# STLINK_V3EC.net
KiCad netlist of a schematic drawn in Altium Designer
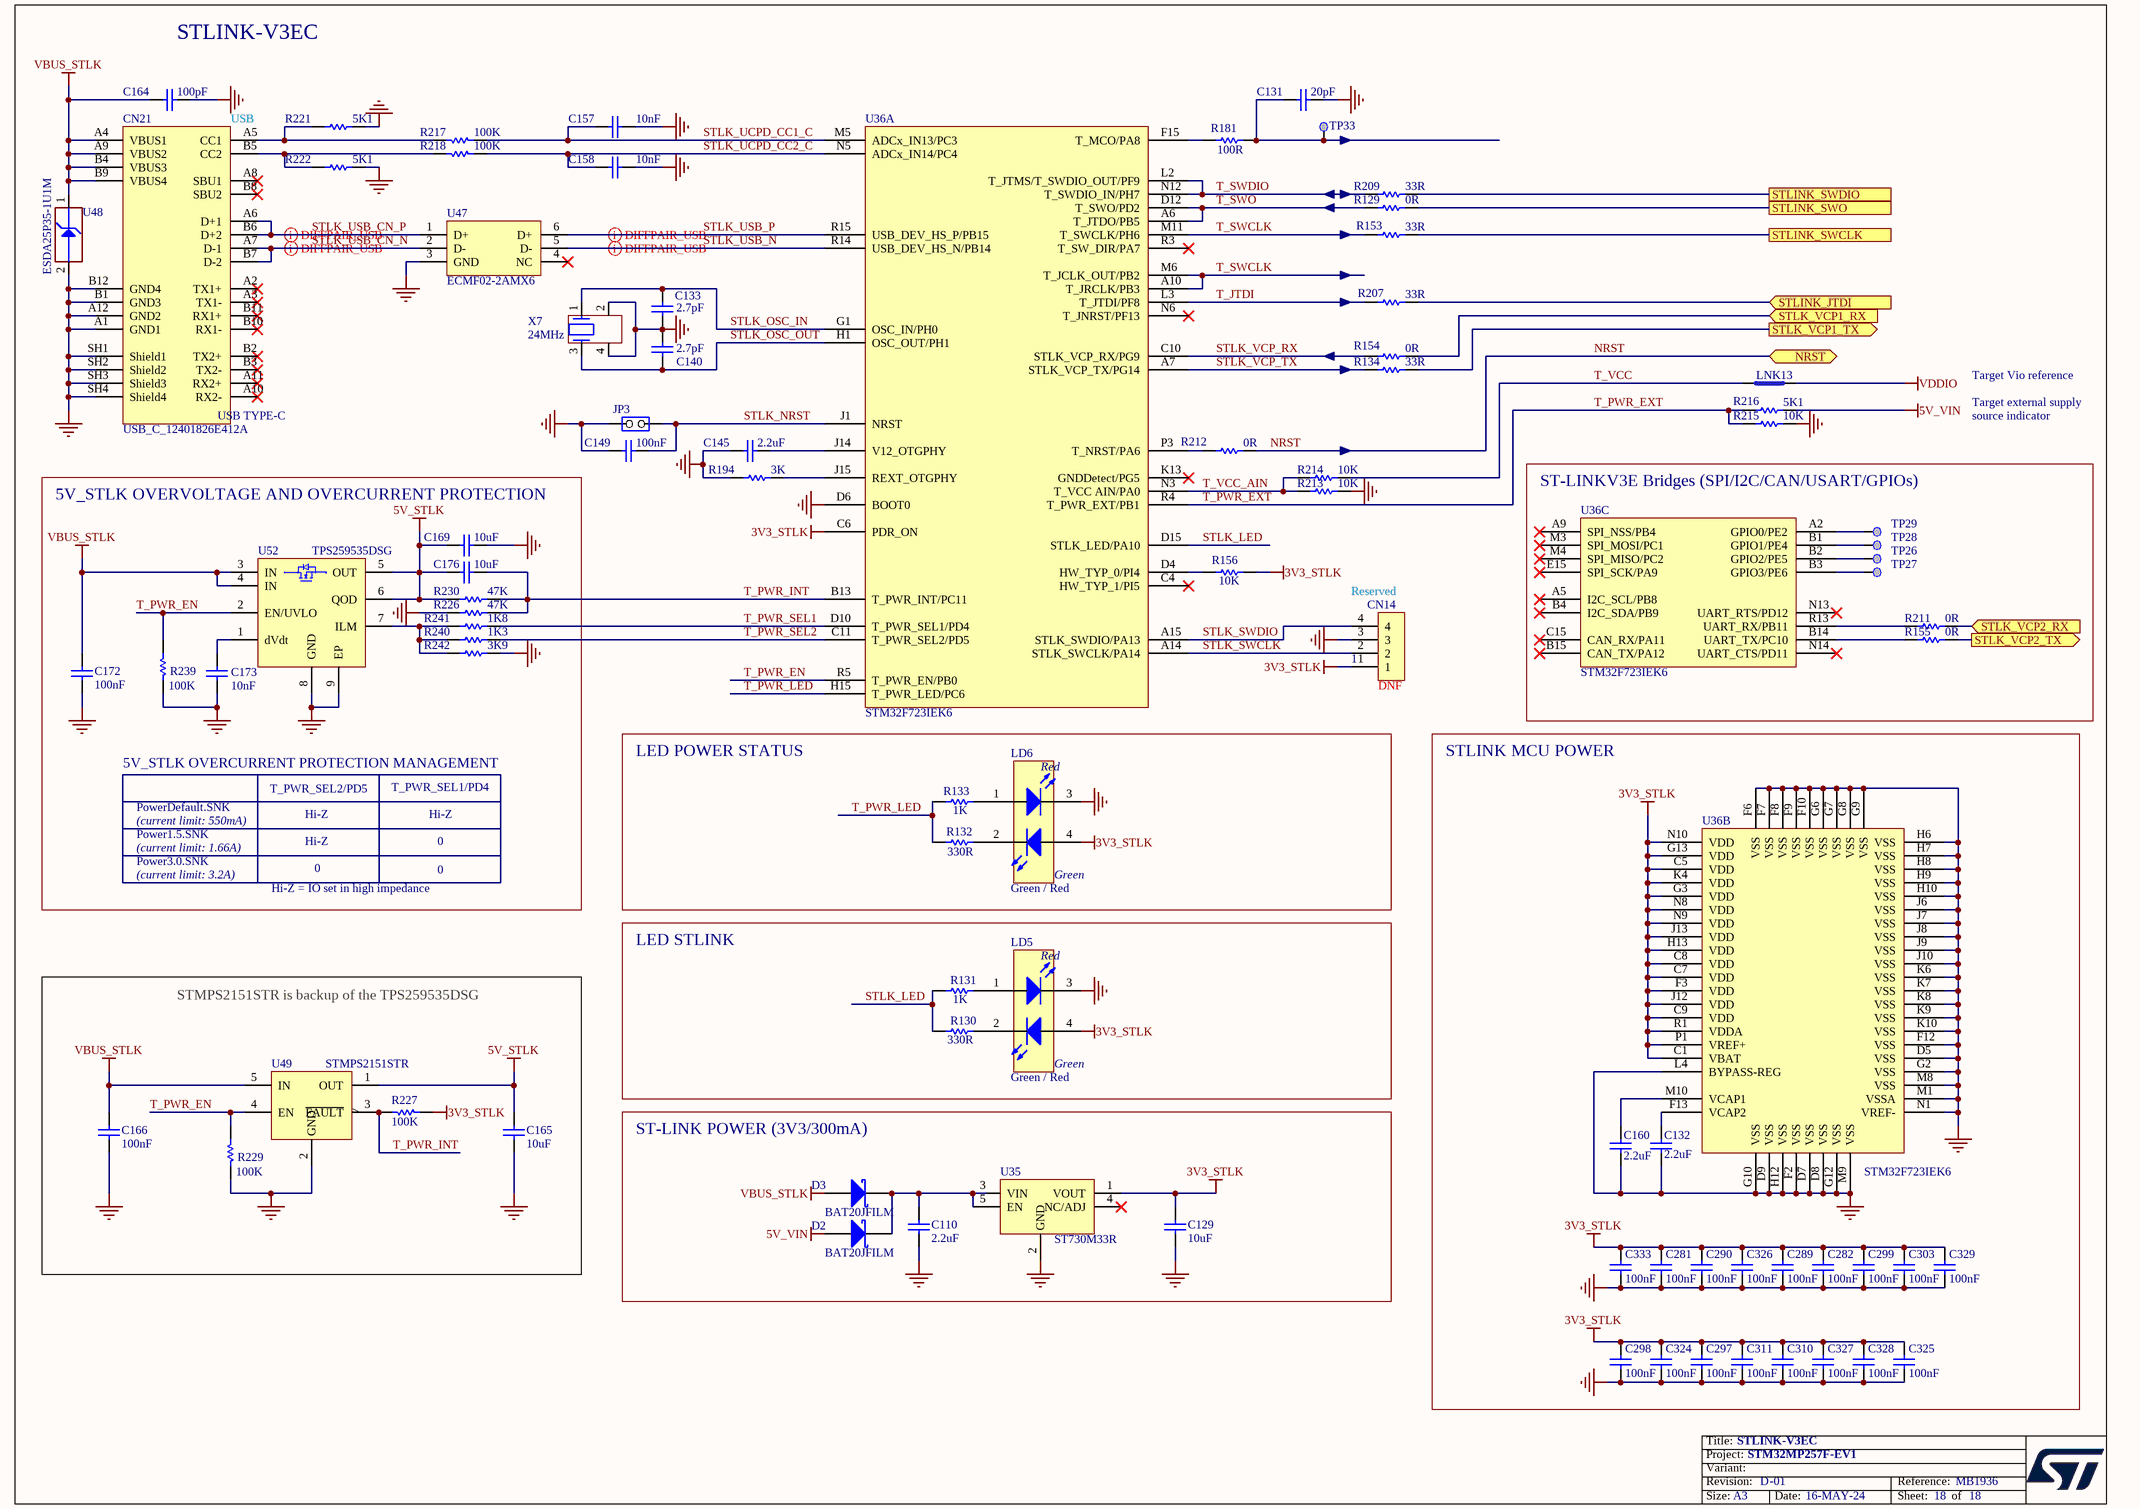
[diagram p0: STLINK_V3EC.SchDoc]

(export (version "E")
  (design (tool "Eeschema 10.0.6"))
  (components
    (comp (ref "C110")
      (value "2.2uF")
      (footprint "MCD_PARTS:C0805")
      (description "Capacitor, MLCC, 2.2uF, 25V, X7R, +/-10%, 0805, T=1,25mm")
      (fields
        (field (name "INTERNAL_PART_NUMBER") "MCD-02372")
        (field (name "MANUFACTURER_PART_NUMBER") "GRM21BR71E225KE11L")
      )
      (libsource (lib "MCD_PARTS_database") (part "Capacitor"))
    )
    (comp (ref "C129")
      (value "10uF")
      (footprint "MCD_PARTS:C0603")
      (description "Capacitor, MLCC, 10uF, 10V, X5R, +/-10%, 0603, T=0.8mm")
      (fields (field (name "INTERNAL_PART_NUMBER") "MCD-00099") (field (name "MANUFACTURER") "MURATA"))
      (libsource (lib "MCD_PARTS_database") (part "Capacitor"))
    )
    (comp (ref "C131")
      (value "20pF")
      (footprint "MCD_PARTS:C0402")
      (description "Capacitor, MLCC, 20pF, 50V, NPO, +/- 5%, 0402, T=0.5mm")
      (fields
        (field (name "INTERNAL_PART_NUMBER") "MCD-00016")
        (field (name "MANUFACTURER_PART_NUMBER") "CC0402JRNPO9BN200")
      )
      (libsource (lib "MCD_PARTS_database") (part "Capacitor"))
    )
    (comp (ref "C132")
      (value "2.2uF")
      (footprint "MCD_PARTS:C0402")
      (description "Capacitor, MLCC, 2.2uF, 6.3V, X5R, +/-10%, 0402, T=0.5mm")
      (fields (field (name "INTERNAL_PART_NUMBER") "MCD-02606") (field (name "MANUFACTURER") "YAGEO"))
      (libsource (lib "MCD_PARTS_database") (part "Capacitor"))
    )
    (comp (ref "C133")
      (value "2.7pF")
      (footprint "MCD_PARTS:C0402")
      (description "Capacitor, MLCC, 2.7pF, 50V, NPO, +/-0.1pF, 0402, T=0.5mm")
      (fields (field (name "INTERNAL_PART_NUMBER") "MCD-01774") (field (name "MANUFACTURER") "YAGEO"))
      (libsource (lib "MCD_PARTS_database") (part "Capacitor"))
    )
    (comp (ref "C140")
      (value "2.7pF")
      (footprint "MCD_PARTS:C0402")
      (description "Capacitor, MLCC, 2.7pF, 50V, NPO, +/-0.1pF, 0402, T=0.5mm")
      (fields (field (name "INTERNAL_PART_NUMBER") "MCD-01774") (field (name "MANUFACTURER") "YAGEO"))
      (libsource (lib "MCD_PARTS_database") (part "Capacitor"))
    )
    (comp (ref "C145")
      (value "2.2uF")
      (footprint "MCD_PARTS:C0402")
      (description "Capacitor, MLCC, 2.2uF, 6.3V, X5R, +/-10%, 0402, T=0.5mm")
      (fields (field (name "INTERNAL_PART_NUMBER") "MCD-02606") (field (name "MANUFACTURER") "YAGEO"))
      (libsource (lib "MCD_PARTS_database") (part "Capacitor"))
    )
    (comp (ref "C149")
      (value "100nF")
      (footprint "MCD_PARTS:C0402")
      (description "Capacitor, MLCC, 100nF, 16V, X7R, +/-10%, 0402, T=0.5mm")
      (fields
        (field (name "INTERNAL_PART_NUMBER") "MCD-00006")
        (field (name "MANUFACTURER_PART_NUMBER") "CC0402KRX7R7BB104")
      )
      (libsource (lib "MCD_PARTS_database") (part "Capacitor"))
    )
    (comp (ref "C157")
      (value "10nF")
      (footprint "MCD_PARTS:C0402")
      (description "Capacitor, MLCC, 10nF, 50V, X7R, +/-10%, 0402, T=0.5mm")
      (fields (field (name "INTERNAL_PART_NUMBER") "MCD-02198") (field (name "MANUFACTURER") "YAGEO"))
      (libsource (lib "MCD_PARTS_database") (part "Capacitor"))
    )
    (comp (ref "C158")
      (value "10nF")
      (footprint "MCD_PARTS:C0402")
      (description "Capacitor, MLCC, 10nF, 50V, X7R, +/-10%, 0402, T=0.5mm")
      (fields (field (name "INTERNAL_PART_NUMBER") "MCD-02198") (field (name "MANUFACTURER") "YAGEO"))
      (libsource (lib "MCD_PARTS_database") (part "Capacitor"))
    )
    (comp (ref "C160")
      (value "2.2uF")
      (footprint "MCD_PARTS:C0402")
      (description "Capacitor, MLCC, 2.2uF, 6.3V, X5R, +/-10%, 0402, T=0.5mm")
      (fields (field (name "INTERNAL_PART_NUMBER") "MCD-02606") (field (name "MANUFACTURER") "YAGEO"))
      (libsource (lib "MCD_PARTS_database") (part "Capacitor"))
    )
    (comp (ref "C164")
      (value "100pF")
      (footprint "MCD_PARTS:C0402")
      (description "Capacitor, MLCC, 100pF, 50V, NPO, +/-5%, 0402, T=0.5mm")
      (fields (field (name "INTERNAL_PART_NUMBER") "MCD-00205") (field (name "MANUFACTURER") "YAGEO"))
      (libsource (lib "MCD_PARTS_database") (part "Capacitor"))
    )
    (comp (ref "C165")
      (value "10uF")
      (footprint "MCD_PARTS:C0603")
      (description "Capacitor, MLCC, 10uF, 10V, X5R, +/-10%, 0603, T=0.8mm")
      (fields (field (name "INTERNAL_PART_NUMBER") "MCD-00099") (field (name "MANUFACTURER") "MURATA"))
      (libsource (lib "MCD_PARTS_database") (part "Capacitor"))
    )
    (comp (ref "C166")
      (value "100nF")
      (footprint "MCD_PARTS:C0402")
      (description "Capacitor, MLCC, 100nF, 25V, X7R, +/-10%, 0402, T=0.5mm")
      (fields (field (name "INTERNAL_PART_NUMBER") "MCD-02355") (field (name "MANUFACTURER") "WALSIN"))
      (libsource (lib "MCD_PARTS_database") (part "Capacitor"))
    )
    (comp (ref "C169")
      (value "10uF")
      (footprint "MCD_PARTS:C0603")
      (description "Capacitor, MLCC, 10uF, 10V, X5R, +/-10%, 0603, T=0.8mm")
      (fields (field (name "INTERNAL_PART_NUMBER") "MCD-00099") (field (name "MANUFACTURER") "MURATA"))
      (libsource (lib "MCD_PARTS_database") (part "Capacitor"))
    )
    (comp (ref "C172")
      (value "100nF")
      (footprint "MCD_PARTS:C0402")
      (description "Capacitor, MLCC, 100nF, 25V, X7R, +/-10%, 0402, T=0.5mm")
      (fields (field (name "INTERNAL_PART_NUMBER") "MCD-02355") (field (name "MANUFACTURER") "WALSIN"))
      (libsource (lib "MCD_PARTS_database") (part "Capacitor"))
    )
    (comp (ref "C173")
      (value "10nF")
      (footprint "MCD_PARTS:C0402")
      (description "Capacitor, MLCC, 10nF, 50V, X7R, +/-10%, 0402, T=0.5mm")
      (fields (field (name "INTERNAL_PART_NUMBER") "MCD-02198") (field (name "MANUFACTURER") "YAGEO"))
      (libsource (lib "MCD_PARTS_database") (part "Capacitor"))
    )
    (comp (ref "C176")
      (value "10uF")
      (footprint "MCD_PARTS:C0402")
      (description "Capacitor, MLCC, 10uF, 6.3V, X5R, +/-20%, 0402, T=0.5mm")
      (fields (field (name "INTERNAL_PART_NUMBER") "MCD-03140") (field (name "MANUFACTURER") "MURATA"))
      (libsource (lib "MCD_PARTS_database") (part "Capacitor"))
    )
    (comp (ref "C281")
      (value "100nF")
      (footprint "MCD_PARTS:C0402")
      (description "Capacitor, MLCC, 100nF, 16V, X7R, +/-10%, 0402, T=0.5mm")
      (fields
        (field (name "INTERNAL_PART_NUMBER") "MCD-00006")
        (field (name "MANUFACTURER_PART_NUMBER") "CC0402KRX7R7BB104")
      )
      (libsource (lib "MCD_PARTS_database") (part "Capacitor"))
    )
    (comp (ref "C282")
      (value "100nF")
      (footprint "MCD_PARTS:C0402")
      (description "Capacitor, MLCC, 100nF, 16V, X7R, +/-10%, 0402, T=0.5mm")
      (fields
        (field (name "INTERNAL_PART_NUMBER") "MCD-00006")
        (field (name "MANUFACTURER_PART_NUMBER") "CC0402KRX7R7BB104")
      )
      (libsource (lib "MCD_PARTS_database") (part "Capacitor"))
    )
    (comp (ref "C289")
      (value "100nF")
      (footprint "MCD_PARTS:C0402")
      (description "Capacitor, MLCC, 100nF, 16V, X7R, +/-10%, 0402, T=0.5mm")
      (fields
        (field (name "INTERNAL_PART_NUMBER") "MCD-00006")
        (field (name "MANUFACTURER_PART_NUMBER") "CC0402KRX7R7BB104")
      )
      (libsource (lib "MCD_PARTS_database") (part "Capacitor"))
    )
    (comp (ref "C290")
      (value "100nF")
      (footprint "MCD_PARTS:C0402")
      (description "Capacitor, MLCC, 100nF, 16V, X7R, +/-10%, 0402, T=0.5mm")
      (fields
        (field (name "INTERNAL_PART_NUMBER") "MCD-00006")
        (field (name "MANUFACTURER_PART_NUMBER") "CC0402KRX7R7BB104")
      )
      (libsource (lib "MCD_PARTS_database") (part "Capacitor"))
    )
    (comp (ref "C297")
      (value "100nF")
      (footprint "MCD_PARTS:C0402")
      (description "Capacitor, MLCC, 100nF, 16V, X7R, +/-10%, 0402, T=0.5mm")
      (fields
        (field (name "INTERNAL_PART_NUMBER") "MCD-00006")
        (field (name "MANUFACTURER_PART_NUMBER") "CC0402KRX7R7BB104")
      )
      (libsource (lib "MCD_PARTS_database") (part "Capacitor"))
    )
    (comp (ref "C298")
      (value "100nF")
      (footprint "MCD_PARTS:C0402")
      (description "Capacitor, MLCC, 100nF, 16V, X7R, +/-10%, 0402, T=0.5mm")
      (fields
        (field (name "INTERNAL_PART_NUMBER") "MCD-00006")
        (field (name "MANUFACTURER_PART_NUMBER") "CC0402KRX7R7BB104")
      )
      (libsource (lib "MCD_PARTS_database") (part "Capacitor"))
    )
    (comp (ref "C299")
      (value "100nF")
      (footprint "MCD_PARTS:C0402")
      (description "Capacitor, MLCC, 100nF, 16V, X7R, +/-10%, 0402, T=0.5mm")
      (fields
        (field (name "INTERNAL_PART_NUMBER") "MCD-00006")
        (field (name "MANUFACTURER_PART_NUMBER") "CC0402KRX7R7BB104")
      )
      (libsource (lib "MCD_PARTS_database") (part "Capacitor"))
    )
    (comp (ref "C303")
      (value "100nF")
      (footprint "MCD_PARTS:C0402")
      (description "Capacitor, MLCC, 100nF, 16V, X7R, +/-10%, 0402, T=0.5mm")
      (fields
        (field (name "INTERNAL_PART_NUMBER") "MCD-00006")
        (field (name "MANUFACTURER_PART_NUMBER") "CC0402KRX7R7BB104")
      )
      (libsource (lib "MCD_PARTS_database") (part "Capacitor"))
    )
    (comp (ref "C310")
      (value "100nF")
      (footprint "MCD_PARTS:C0402")
      (description "Capacitor, MLCC, 100nF, 16V, X7R, +/-10%, 0402, T=0.5mm")
      (fields
        (field (name "INTERNAL_PART_NUMBER") "MCD-00006")
        (field (name "MANUFACTURER_PART_NUMBER") "CC0402KRX7R7BB104")
      )
      (libsource (lib "MCD_PARTS_database") (part "Capacitor"))
    )
    (comp (ref "C311")
      (value "100nF")
      (footprint "MCD_PARTS:C0402")
      (description "Capacitor, MLCC, 100nF, 16V, X7R, +/-10%, 0402, T=0.5mm")
      (fields
        (field (name "INTERNAL_PART_NUMBER") "MCD-00006")
        (field (name "MANUFACTURER_PART_NUMBER") "CC0402KRX7R7BB104")
      )
      (libsource (lib "MCD_PARTS_database") (part "Capacitor"))
    )
    (comp (ref "C324")
      (value "100nF")
      (footprint "MCD_PARTS:C0402")
      (description "Capacitor, MLCC, 100nF, 16V, X7R, +/-10%, 0402, T=0.5mm")
      (fields
        (field (name "INTERNAL_PART_NUMBER") "MCD-00006")
        (field (name "MANUFACTURER_PART_NUMBER") "CC0402KRX7R7BB104")
      )
      (libsource (lib "MCD_PARTS_database") (part "Capacitor"))
    )
    (comp (ref "C325")
      (value "100nF")
      (footprint "MCD_PARTS:C0402")
      (description "Capacitor, MLCC, 100nF, 16V, X7R, +/-10%, 0402, T=0.5mm")
      (fields
        (field (name "INTERNAL_PART_NUMBER") "MCD-00006")
        (field (name "MANUFACTURER_PART_NUMBER") "CC0402KRX7R7BB104")
      )
      (libsource (lib "MCD_PARTS_database") (part "Capacitor"))
    )
    (comp (ref "C326")
      (value "100nF")
      (footprint "MCD_PARTS:C0402")
      (description "Capacitor, MLCC, 100nF, 16V, X7R, +/-10%, 0402, T=0.5mm")
      (fields
        (field (name "INTERNAL_PART_NUMBER") "MCD-00006")
        (field (name "MANUFACTURER_PART_NUMBER") "CC0402KRX7R7BB104")
      )
      (libsource (lib "MCD_PARTS_database") (part "Capacitor"))
    )
    (comp (ref "C327")
      (value "100nF")
      (footprint "MCD_PARTS:C0402")
      (description "Capacitor, MLCC, 100nF, 16V, X7R, +/-10%, 0402, T=0.5mm")
      (fields
        (field (name "INTERNAL_PART_NUMBER") "MCD-00006")
        (field (name "MANUFACTURER_PART_NUMBER") "CC0402KRX7R7BB104")
      )
      (libsource (lib "MCD_PARTS_database") (part "Capacitor"))
    )
    (comp (ref "C328")
      (value "100nF")
      (footprint "MCD_PARTS:C0402")
      (description "Capacitor, MLCC, 100nF, 16V, X7R, +/-10%, 0402, T=0.5mm")
      (fields
        (field (name "INTERNAL_PART_NUMBER") "MCD-00006")
        (field (name "MANUFACTURER_PART_NUMBER") "CC0402KRX7R7BB104")
      )
      (libsource (lib "MCD_PARTS_database") (part "Capacitor"))
    )
    (comp (ref "C329")
      (value "100nF")
      (footprint "MCD_PARTS:C0402")
      (description "Capacitor, MLCC, 100nF, 16V, X7R, +/-10%, 0402, T=0.5mm")
      (fields
        (field (name "INTERNAL_PART_NUMBER") "MCD-00006")
        (field (name "MANUFACTURER_PART_NUMBER") "CC0402KRX7R7BB104")
      )
      (libsource (lib "MCD_PARTS_database") (part "Capacitor"))
    )
    (comp (ref "C333")
      (value "100nF")
      (footprint "MCD_PARTS:C0402")
      (description "Capacitor, MLCC, 100nF, 16V, X7R, +/-10%, 0402, T=0.5mm")
      (fields
        (field (name "INTERNAL_PART_NUMBER") "MCD-00006")
        (field (name "MANUFACTURER_PART_NUMBER") "CC0402KRX7R7BB104")
      )
      (libsource (lib "MCD_PARTS_database") (part "Capacitor"))
    )
    (comp (ref "CN14")
      (value "Header 4x1")
      (footprint "MCD_PARTS:CON_SAMTEC_TSW-104-07-G-S")
      (description "Header, 4x1, 2.54mm, VR, TH, T=5.84mm/2.54mm")
      (fields
        (field (name "INTERNAL_PART_NUMBER") "MCD-00029")
        (field (name "MANUFACTURER_PART_NUMBER") "TSW-104-07-G-S")
      )
      (libsource (lib "MCD_PARTS_database") (part "Header 4x1"))
    )
    (comp (ref "CN21")
      (value "USB_C_12401826E412A")
      (footprint "MCD_PARTS:CON_USB-TYPEC_AMPHENOL_12401826E412A")
      (description "USB_TypeC, 24 pins, RA, SMD, T=2.96mm")
      (fields (field (name "INTERNAL_PART_NUMBER") "MCD-03232") (field (name "MANUFACTURER") "AMPHENOL ICC"))
      (libsource (lib "MCD_PARTS_database") (part "USB_TYPE_C_Receptacle"))
    )
    (comp (ref "D2")
      (value "BAT20JFILM")
      (footprint "MCD_PARTS:DIO_SOD323_1A_2K")
      (description "Signal Schottky Diode, If=1A, Ifsm=5A, Vf =0.54V@1A, Vrrm=23V, Ir = 0.65µA@5V, SOD-323")
      (fields
        (field (name "INTERNAL_PART_NUMBER") "MCD-03011")
        (field (name "MANUFACTURER") "STMICROELECTRONICS")
      )
      (libsource (lib "MCD_PARTS_database") (part "SCHOTTKY_1A_2K"))
    )
    (comp (ref "D3")
      (value "BAT20JFILM")
      (footprint "MCD_PARTS:DIO_SOD323_1A_2K")
      (description "Signal Schottky Diode, If=1A, Ifsm=5A, Vf =0.54V@1A, Vrrm=23V, Ir = 0.65µA@5V, SOD-323")
      (fields
        (field (name "INTERNAL_PART_NUMBER") "MCD-03011")
        (field (name "MANUFACTURER") "STMICROELECTRONICS")
      )
      (libsource (lib "MCD_PARTS_database") (part "SCHOTTKY_1A_2K"))
    )
    (comp (ref "JP3")
      (value "Jumper_Header 2x1")
      (footprint "MCD_PARTS:CON_SAMTEC_TSW-102-07-G-S")
      (description "Header, 2x1, 2.54mm, VR, TH, T=5.84mm/2.54mm")
      (fields (field (name "INTERNAL_PART_NUMBER") "MCD-00045") (field (name "MANUFACTURER") "SAMTEC"))
      (libsource (lib "MCD_PARTS_database") (part "Jumper_Header 2x1"))
    )
    (comp (ref "LD5")
      (value "Green / Red")
      (footprint "MCD_PARTS:LED_BI-GR_WE-150141SV73110")
      (description "LED Bicolor, Green/Red, 2V, 20mA,  4-PLCC")
      (fields
        (field (name "INTERNAL_PART_NUMBER") "MCD-02631")
        (field (name "MANUFACTURER") "WURTH ELEKTRONIK")
      )
      (libsource (lib "MCD_PARTS_database") (part "LED_BICOLOR"))
    )
    (comp (ref "LD6")
      (value "Green / Red")
      (footprint "MCD_PARTS:LED_BI-GR_WE-150141SV73110")
      (description "LED Bicolor, Green/Red, 2V, 20mA,  4-PLCC")
      (fields
        (field (name "INTERNAL_PART_NUMBER") "MCD-02631")
        (field (name "MANUFACTURER") "WURTH ELEKTRONIK")
      )
      (libsource (lib "MCD_PARTS_database") (part "LED_BICOLOR"))
    )
    (comp (ref "LNK13")
      (value "link_200")
      (footprint "MCD_PARTS:LINK200")
      (description "Track link on PCB 200um width for layout routing. No component assembly and no component in BOM")
      (fields (field (name "INTERNAL_PART_NUMBER") "MCD-02777"))
      (libsource (lib "MCD_PARTS_database") (part "link_200"))
    )
    (comp (ref "R129")
      (value "0R")
      (footprint "MCD_PARTS:R0402")
      (description "Resistor, 0R, 0402, +/-5%, 1/16W")
      (fields (field (name "INTERNAL_PART_NUMBER") "MCD-00052") (field (name "MANUFACTURER") "YAGEO"))
      (libsource (lib "MCD_PARTS_database") (part "Resistor"))
    )
    (comp (ref "R130")
      (value "330R")
      (footprint "MCD_PARTS:R0402")
      (description "Resistor, 330R, 0402, +/-1%, 1/16W")
      (fields (field (name "INTERNAL_PART_NUMBER") "MCD-00062") (field (name "MANUFACTURER") "YAGEO"))
      (libsource (lib "MCD_PARTS_database") (part "Resistor"))
    )
    (comp (ref "R131")
      (value "1K")
      (footprint "MCD_PARTS:R0402")
      (description "Resistor, 1K, 0402, +/-0.1%, 1/16W, +/-25ppm/°C")
      (fields (field (name "INTERNAL_PART_NUMBER") "MCD-02665") (field (name "MANUFACTURER") "YAGEO"))
      (libsource (lib "MCD_PARTS_database") (part "Resistor"))
    )
    (comp (ref "R132")
      (value "330R")
      (footprint "MCD_PARTS:R0402")
      (description "Resistor, 330R, 0402, +/-1%, 1/16W")
      (fields (field (name "INTERNAL_PART_NUMBER") "MCD-00062") (field (name "MANUFACTURER") "YAGEO"))
      (libsource (lib "MCD_PARTS_database") (part "Resistor"))
    )
    (comp (ref "R133")
      (value "1K")
      (footprint "MCD_PARTS:R0402")
      (description "Resistor, 1K, 0402, +/-0.1%, 1/16W, +/-25ppm/°C")
      (fields (field (name "INTERNAL_PART_NUMBER") "MCD-02665") (field (name "MANUFACTURER") "YAGEO"))
      (libsource (lib "MCD_PARTS_database") (part "Resistor"))
    )
    (comp (ref "R134")
      (value "33R")
      (footprint "MCD_PARTS:R0402")
      (description "Resistor, 33R, 0402, +/-1%, 1/16W")
      (fields (field (name "INTERNAL_PART_NUMBER") "MCD-00455") (field (name "MANUFACTURER") "YAGEO"))
      (libsource (lib "MCD_PARTS_database") (part "Resistor"))
    )
    (comp (ref "R153")
      (value "33R")
      (footprint "MCD_PARTS:R0402")
      (description "Resistor, 33R, 0402, +/-1%, 1/16W")
      (fields (field (name "INTERNAL_PART_NUMBER") "MCD-00455") (field (name "MANUFACTURER") "YAGEO"))
      (libsource (lib "MCD_PARTS_database") (part "Resistor"))
    )
    (comp (ref "R154")
      (value "0R")
      (footprint "MCD_PARTS:R0402")
      (description "Resistor, 0R, 0402, +/-5%, 1/16W")
      (fields (field (name "INTERNAL_PART_NUMBER") "MCD-00052") (field (name "MANUFACTURER") "YAGEO"))
      (libsource (lib "MCD_PARTS_database") (part "Resistor"))
    )
    (comp (ref "R155")
      (value "0R")
      (footprint "MCD_PARTS:R0402")
      (description "Resistor, 0R, 0402, +/-5%, 1/16W")
      (fields
        (field (name "INTERNAL_PART_NUMBER") "MCD-00052")
        (field (name "MANUFACTURER_PART_NUMBER") "RC0402JR-070RL")
      )
      (libsource (lib "MCD_PARTS_database") (part "Resistor"))
    )
    (comp (ref "R156")
      (value "10K")
      (footprint "MCD_PARTS:R0402")
      (description "Resistor, 10K, 0402, +/-1%, 1/16W")
      (fields
        (field (name "INTERNAL_PART_NUMBER") "MCD-00053")
        (field (name "MANUFACTURER_PART_NUMBER") "RC0402FR-0710KL")
      )
      (libsource (lib "MCD_PARTS_database") (part "Resistor"))
    )
    (comp (ref "R181")
      (value "100R")
      (footprint "MCD_PARTS:R0402")
      (description "Resistor, 100R, 0402, +/- 1%, 1/16W")
      (fields (field (name "INTERNAL_PART_NUMBER") "MCD-00067") (field (name "MANUFACTURER") "YAGEO"))
      (libsource (lib "MCD_PARTS_database") (part "Resistor"))
    )
    (comp (ref "R194")
      (value "3K")
      (footprint "MCD_PARTS:R0402")
      (description "Resistor, 3K, 0402, +/-1%, 1/16W")
      (fields
        (field (name "INTERNAL_PART_NUMBER") "MCD-00185")
        (field (name "MANUFACTURER_PART_NUMBER") "RC0402FR-073KL")
      )
      (libsource (lib "MCD_PARTS_database") (part "Resistor"))
    )
    (comp (ref "R207")
      (value "33R")
      (footprint "MCD_PARTS:R0402")
      (description "Resistor, 33R, 0402, +/-1%, 1/16W")
      (fields (field (name "INTERNAL_PART_NUMBER") "MCD-00455") (field (name "MANUFACTURER") "YAGEO"))
      (libsource (lib "MCD_PARTS_database") (part "Resistor"))
    )
    (comp (ref "R209")
      (value "33R")
      (footprint "MCD_PARTS:R0402")
      (description "Resistor, 33R, 0402, +/-1%, 1/16W")
      (fields (field (name "INTERNAL_PART_NUMBER") "MCD-00455") (field (name "MANUFACTURER") "YAGEO"))
      (libsource (lib "MCD_PARTS_database") (part "Resistor"))
    )
    (comp (ref "R211")
      (value "0R")
      (footprint "MCD_PARTS:R0402")
      (description "Resistor, 0R, 0402, +/-5%, 1/16W")
      (fields
        (field (name "INTERNAL_PART_NUMBER") "MCD-00052")
        (field (name "MANUFACTURER_PART_NUMBER") "RC0402JR-070RL")
      )
      (libsource (lib "MCD_PARTS_database") (part "Resistor"))
    )
    (comp (ref "R212")
      (value "0R")
      (footprint "MCD_PARTS:R0402")
      (description "Resistor, 0R, 0402, +/-5%, 1/16W")
      (fields (field (name "INTERNAL_PART_NUMBER") "MCD-00052") (field (name "MANUFACTURER") "YAGEO"))
      (libsource (lib "MCD_PARTS_database") (part "Resistor"))
    )
    (comp (ref "R213")
      (value "10K")
      (footprint "MCD_PARTS:R0402")
      (description "Resistor, 10K, 0402, +/-1%, 1/16W")
      (fields
        (field (name "INTERNAL_PART_NUMBER") "MCD-00053")
        (field (name "MANUFACTURER_PART_NUMBER") "RC0402FR-0710KL")
      )
      (libsource (lib "MCD_PARTS_database") (part "Resistor"))
    )
    (comp (ref "R214")
      (value "10K")
      (footprint "MCD_PARTS:R0402")
      (description "Resistor, 10K, 0402, +/-1%, 1/16W")
      (fields
        (field (name "INTERNAL_PART_NUMBER") "MCD-00053")
        (field (name "MANUFACTURER_PART_NUMBER") "RC0402FR-0710KL")
      )
      (libsource (lib "MCD_PARTS_database") (part "Resistor"))
    )
    (comp (ref "R215")
      (value "10K")
      (footprint "MCD_PARTS:R0402")
      (description "Resistor, 10K, 0402, +/-1%, 1/16W")
      (fields
        (field (name "INTERNAL_PART_NUMBER") "MCD-00053")
        (field (name "MANUFACTURER_PART_NUMBER") "RC0402FR-0710KL")
      )
      (libsource (lib "MCD_PARTS_database") (part "Resistor"))
    )
    (comp (ref "R216")
      (value "5K1")
      (footprint "MCD_PARTS:R0402")
      (description "Resistor, 5K1, 0402, +/-1%, 1/16W")
      (fields (field (name "INTERNAL_PART_NUMBER") "MCD-00333") (field (name "MANUFACTURER") "YAGEO"))
      (libsource (lib "MCD_PARTS_database") (part "Resistor"))
    )
    (comp (ref "R217")
      (value "100K")
      (footprint "MCD_PARTS:R0402")
      (description "Resistor, 100K, 0402, +/-1%, 1/16W")
      (fields
        (field (name "INTERNAL_PART_NUMBER") "MCD-00059")
        (field (name "MANUFACTURER_PART_NUMBER") "RC0402FR-07100KL")
      )
      (libsource (lib "MCD_PARTS_database") (part "Resistor"))
    )
    (comp (ref "R218")
      (value "100K")
      (footprint "MCD_PARTS:R0402")
      (description "Resistor, 100K, 0402, +/-1%, 1/16W")
      (fields
        (field (name "INTERNAL_PART_NUMBER") "MCD-00059")
        (field (name "MANUFACTURER_PART_NUMBER") "RC0402FR-07100KL")
      )
      (libsource (lib "MCD_PARTS_database") (part "Resistor"))
    )
    (comp (ref "R221")
      (value "5K1")
      (footprint "MCD_PARTS:R0402")
      (description "Resistor, 5K1, 0402, +/-1%, 1/16W")
      (fields (field (name "INTERNAL_PART_NUMBER") "MCD-00333") (field (name "MANUFACTURER") "YAGEO"))
      (libsource (lib "MCD_PARTS_database") (part "Resistor"))
    )
    (comp (ref "R222")
      (value "5K1")
      (footprint "MCD_PARTS:R0402")
      (description "Resistor, 5K1, 0402, +/-1%, 1/16W")
      (fields (field (name "INTERNAL_PART_NUMBER") "MCD-00333") (field (name "MANUFACTURER") "YAGEO"))
      (libsource (lib "MCD_PARTS_database") (part "Resistor"))
    )
    (comp (ref "R226")
      (value "47K")
      (footprint "MCD_PARTS:R0402")
      (description "Resistor,47K,0402,1%,1/16W")
      (fields
        (field (name "INTERNAL_PART_NUMBER") "MCD-00063")
        (field (name "MANUFACTURER_PART_NUMBER") "RC0402FR-0747KL")
        (field (name "PROVIDED_BY") "SUBCO")
      )
      (libsource (lib "MCD_PARTS_database") (part "Resistor"))
    )
    (comp (ref "R227")
      (value "100K")
      (footprint "MCD_PARTS:R0402")
      (description "Resistor, 100K, 0402, +/-1%, 1/16W")
      (fields
        (field (name "INTERNAL_PART_NUMBER") "MCD-00059")
        (field (name "MANUFACTURER_PART_NUMBER") "RC0402FR-07100KL")
      )
      (libsource (lib "MCD_PARTS_database") (part "Resistor"))
    )
    (comp (ref "R229")
      (value "100K")
      (footprint "MCD_PARTS:R0402")
      (description "Resistor, 100K, 0402, +/-1%, 1/16W")
      (fields
        (field (name "INTERNAL_PART_NUMBER") "MCD-00059")
        (field (name "MANUFACTURER_PART_NUMBER") "RC0402FR-07100KL")
      )
      (libsource (lib "MCD_PARTS_database") (part "Resistor"))
    )
    (comp (ref "R230")
      (value "47K")
      (footprint "MCD_PARTS:R0402")
      (description "Resistor,47K,0402,1%,1/16W")
      (fields
        (field (name "INTERNAL_PART_NUMBER") "MCD-00063")
        (field (name "MANUFACTURER_PART_NUMBER") "RC0402FR-0747KL")
        (field (name "PROVIDED_BY") "SUBCO")
      )
      (libsource (lib "MCD_PARTS_database") (part "Resistor"))
    )
    (comp (ref "R239")
      (value "100K")
      (footprint "MCD_PARTS:R0402")
      (description "Resistor, 100K, 0402, +/-1%, 1/16W")
      (fields
        (field (name "INTERNAL_PART_NUMBER") "MCD-00059")
        (field (name "MANUFACTURER_PART_NUMBER") "RC0402FR-07100KL")
      )
      (libsource (lib "MCD_PARTS_database") (part "Resistor"))
    )
    (comp (ref "R240")
      (value "1K3")
      (footprint "MCD_PARTS:R0402")
      (description "Resistor, 1K3, 0402, +/-1%, 1/16W")
      (fields (field (name "INTERNAL_PART_NUMBER") "MCD-00381") (field (name "MANUFACTURER") "YAGEO"))
      (libsource (lib "MCD_PARTS_database") (part "Resistor"))
    )
    (comp (ref "R241")
      (value "1K8")
      (footprint "MCD_PARTS:R0402")
      (description "Resistor, 1K8, 0402, +/-1%, 1/16W")
      (fields (field (name "INTERNAL_PART_NUMBER") "MCD-00409") (field (name "MANUFACTURER") "YAGEO"))
      (libsource (lib "MCD_PARTS_database") (part "Resistor"))
    )
    (comp (ref "R242")
      (value "3K9")
      (footprint "MCD_PARTS:R0402")
      (description "Resistor, 3K9, 0402, +/-1%, 1/16W, +/-100ppm/°C")
      (fields (field (name "INTERNAL_PART_NUMBER") "MCD-02455") (field (name "MANUFACTURER") "YAGEO"))
      (libsource (lib "MCD_PARTS_database") (part "Resistor"))
    )
    (comp (ref "TP26")
      (value "Test Point")
      (footprint "MCD_PARTS:TP_SMD_1MM")
      (description "Test Point 1mm")
      (fields
        (field (name "INTERNAL_PART_NUMBER") "MCD-00074")
        (field (name "MANUFACTURER_PART_NUMBER") "n/a")
      )
      (libsource (lib "MCD_PARTS_database") (part "Test Point"))
    )
    (comp (ref "TP27")
      (value "Test Point")
      (footprint "MCD_PARTS:TP_SMD_1MM")
      (description "Test Point 1mm")
      (fields
        (field (name "INTERNAL_PART_NUMBER") "MCD-00074")
        (field (name "MANUFACTURER_PART_NUMBER") "n/a")
      )
      (libsource (lib "MCD_PARTS_database") (part "Test Point"))
    )
    (comp (ref "TP28")
      (value "Test Point")
      (footprint "MCD_PARTS:TP_SMD_1MM")
      (description "Test Point 1mm")
      (fields
        (field (name "INTERNAL_PART_NUMBER") "MCD-00074")
        (field (name "MANUFACTURER_PART_NUMBER") "n/a")
      )
      (libsource (lib "MCD_PARTS_database") (part "Test Point"))
    )
    (comp (ref "TP29")
      (value "Test Point")
      (footprint "MCD_PARTS:TP_SMD_1MM")
      (description "Test Point 1mm")
      (fields
        (field (name "INTERNAL_PART_NUMBER") "MCD-00074")
        (field (name "MANUFACTURER_PART_NUMBER") "n/a")
      )
      (libsource (lib "MCD_PARTS_database") (part "Test Point"))
    )
    (comp (ref "TP33")
      (value "Test Point")
      (footprint "MCD_PARTS:TP_SMD_1MM")
      (description "Test Point 1mm")
      (fields (field (name "INTERNAL_PART_NUMBER") "MCD-00074"))
      (libsource (lib "") (part "Test Point_1"))
    )
    (comp (ref "U35")
      (value "ST730M33R")
      (footprint "MCD_PARTS:ICC_SOT23-5L_H1P45")
      (description "LDO, 3.3V, 300mA, High input voltage: 2.5V to 28V, SOT23-5L")
      (fields
        (field (name "INTERNAL_PART_NUMBER") "MCD-02514")
        (field (name "MANUFACTURER") "STMICROELECTRONICS")
      )
      (libsource (lib "MCD_PARTS_database") (part "ST730M33R"))
    )
    (comp (ref "U36")
      (value "STM32F723IEK6")
      (footprint "MCD_PARTS:ICC_UFBGA201_176+25_10X10_P065")
      (description "MCU, Arm Cortex-M7 32-bit MCU, 512KB Flash, 276KB RAM, With Crypto")
      (fields (field (name "INTERNAL_PART_NUMBER") "MCD-02706") (field (name "BMS_PART_NUMBER") "9175300"))
      (libsource (lib "MCD_PARTS_database") (part "STLINK-V3EC"))
    )
    (comp (ref "U47")
      (value "ECMF02-2AMX6")
      (footprint "MCD_PARTS:ESD_QFN-6L_1P7X1P5_P050")
      (description "Common mode filter with ESD protection for USB 2.0 interface")
      (fields
        (field (name "INTERNAL_PART_NUMBER") "MCD-00649")
        (field (name "MANUFACTURER") "STMICROELECTRONICS")
      )
      (libsource (lib "MCD_PARTS_database") (part "ECMF02-2AMX6"))
    )
    (comp (ref "U48")
      (value "ESDA25P35-1U1M")
      (footprint "MCD_PARTS:ESD_QFN1610_2N_1K_2A")
      (description "High power Transient voltage suppressor:25V/35A EOS and ESD transients protection.")
      (fields
        (field (name "INTERNAL_PART_NUMBER") "MCD-01207")
        (field (name "MANUFACTURER") "STMICROELECTRONICS")
      )
      (libsource (lib "MCD_PARTS_database") (part "ESD-TRANSIL"))
    )
    (comp (ref "U49")
      (value "STMPS2151STR")
      (footprint "MCD_PARTS:MOS_SOT23-5L")
      (description "500mA, Enhanced single channel power switches with active high enable pin")
      (fields
        (field (name "INTERNAL_PART_NUMBER") "MCD-00159")
        (field (name "MANUFACTURER") "STMICROELECTRONICS")
        (field (name "PROVIDED_BY") "Subcon")
      )
      (libsource (lib "MCD_PARTS_database") (part "STMPS2151STR"))
    )
    (comp (ref "U52")
      (value "TPS259535DSG")
      (footprint "MCD_PARTS:ICC_WSON8-EPAD_2X2_P050")
      (description "IC, eFuse with Fast Overvoltage Protection 2.7V to 18V 4A 34mOhm 8-Pin WSON")
      (fields
        (field (name "INTERNAL_PART_NUMBER") "MCD-02532")
        (field (name "MANUFACTURER") "TEXAS INSTRUMENTS")
      )
      (libsource (lib "MCD_PARTS_database") (part "TPS259535DSG"))
    )
    (comp (ref "X7")
      (value "24MHz")
      (footprint "MCD_PARTS:CRY_NX2016SA_4P")
      (description "Crystal, 24MHz, 6pF, +/-20ppm, 80R, 2x1.6mm")
      (fields (field (name "INTERNAL_PART_NUMBER") "MCD-01036") (field (name "BMS_PART_NUMBER") "9157045"))
      (libsource (lib "MCD_PARTS_database") (part "XTAL_4_PINS"))
    )
  )
  (nets
    (net (code "1") (name "/NRST") (class "Default")
      (node (ref "R212") (pin "2") (pinfunction "2_2") (pintype "passive"))
    )
    (net (code "2") (name "/STLINK_JTDI") (class "Default")
      (node (ref "R207") (pin "2") (pinfunction "2_2") (pintype "passive"))
    )
    (net (code "3") (name "/STLINK_SWCLK") (class "Default")
      (node (ref "R153") (pin "2") (pinfunction "2_2") (pintype "passive"))
    )
    (net (code "4") (name "/STLINK_SWDIO") (class "Default")
      (node (ref "R209") (pin "2") (pinfunction "2_2") (pintype "passive"))
    )
    (net (code "5") (name "/STLINK_SWO") (class "Default")
      (node (ref "R129") (pin "2") (pinfunction "2_2") (pintype "passive"))
    )
    (net (code "6") (name "/STLK_LED") (class "Default")
      (node (ref "R130") (pin "1") (pinfunction "1_1") (pintype "passive"))
      (node (ref "R131") (pin "2") (pinfunction "2_2") (pintype "passive"))
      (node (ref "U36") (pin "D15") (pinfunction "STLK_LED/PA10_D15") (pintype "passive"))
    )
    (net (code "7") (name "/STLK_NRST") (class "Default")
      (node (ref "C149") (pin "2") (pinfunction "2_2") (pintype "passive"))
      (node (ref "JP3") (pin "1") (pinfunction "COMMON_1") (pintype "passive"))
      (node (ref "U36") (pin "J1") (pinfunction "NRST_J1") (pintype "passive"))
    )
    (net (code "8") (name "/STLK_OSC_IN") (class "Default")
      (node (ref "C133") (pin "1") (pinfunction "1_1") (pintype "passive"))
      (node (ref "U36") (pin "G1") (pinfunction "OSC_IN/PH0_G1") (pintype "passive"))
      (node (ref "X7") (pin "1") (pinfunction "1_1") (pintype "passive"))
    )
    (net (code "9") (name "/STLK_OSC_OUT") (class "Default")
      (node (ref "C140") (pin "2") (pinfunction "2_2") (pintype "passive"))
      (node (ref "U36") (pin "H1") (pinfunction "OSC_OUT/PH1_H1") (pintype "passive"))
      (node (ref "X7") (pin "3") (pinfunction "3_3") (pintype "passive"))
    )
    (net (code "10") (name "/STLK_SWCLK") (class "Default")
      (node (ref "CN14") (pin "2") (pinfunction "2_2") (pintype "passive"))
      (node (ref "U36") (pin "A14") (pinfunction "STLK_SWCLK/PA14_A14") (pintype "passive"))
    )
    (net (code "11") (name "/STLK_SWDIO") (class "Default")
      (node (ref "CN14") (pin "4") (pinfunction "4_4") (pintype "passive"))
      (node (ref "U36") (pin "A15") (pinfunction "STLK_SWDIO/PA13_A15") (pintype "passive"))
    )
    (net (code "12") (name "/STLK_UCPD_CC1_C") (class "Default")
      (node (ref "C157") (pin "1") (pinfunction "1_1") (pintype "passive"))
      (node (ref "R217") (pin "1") (pinfunction "1_1") (pintype "passive"))
      (node (ref "U36") (pin "M5") (pinfunction "ADCx_IN13/PC3_M5") (pintype "passive"))
    )
    (net (code "13") (name "/STLK_UCPD_CC2_C") (class "Default")
      (node (ref "C158") (pin "1") (pinfunction "1_1") (pintype "passive"))
      (node (ref "R218") (pin "1") (pinfunction "1_1") (pintype "passive"))
      (node (ref "U36") (pin "N5") (pinfunction "ADCx_IN14/PC4_N5") (pintype "passive"))
    )
    (net (code "14") (name "/STLK_USB_CN_N") (class "Default")
      (node (ref "CN21") (pin "A7") (pinfunction "D-1_A7") (pintype "passive"))
      (node (ref "CN21") (pin "B7") (pinfunction "D-2_B7") (pintype "passive"))
      (node (ref "U47") (pin "2") (pinfunction "D-_2") (pintype "passive"))
    )
    (net (code "15") (name "/STLK_USB_CN_P") (class "Default")
      (node (ref "CN21") (pin "A6") (pinfunction "D+1_A6") (pintype "passive"))
      (node (ref "CN21") (pin "B6") (pinfunction "D+2_B6") (pintype "passive"))
      (node (ref "U47") (pin "1") (pinfunction "D+_1") (pintype "passive"))
    )
    (net (code "16") (name "/STLK_USB_N") (class "Default")
      (node (ref "U36") (pin "R14") (pinfunction "USB_DEV_HS_N/PB14_R14") (pintype "passive"))
      (node (ref "U47") (pin "5") (pinfunction "D-_5") (pintype "passive"))
    )
    (net (code "17") (name "/STLK_USB_P") (class "Default")
      (node (ref "U36") (pin "R15") (pinfunction "USB_DEV_HS_P/PB15_R15") (pintype "passive"))
      (node (ref "U47") (pin "6") (pinfunction "D+_6") (pintype "passive"))
    )
    (net (code "18") (name "/STLK_VCP1_RX") (class "Default")
      (node (ref "R154") (pin "2") (pinfunction "2_2") (pintype "passive"))
    )
    (net (code "19") (name "/STLK_VCP1_TX") (class "Default")
      (node (ref "R134") (pin "2") (pinfunction "2_2") (pintype "passive"))
    )
    (net (code "20") (name "/STLK_VCP2_RX") (class "Default")
      (node (ref "R211") (pin "1") (pinfunction "1_1") (pintype "passive"))
    )
    (net (code "21") (name "/STLK_VCP2_TX") (class "Default")
      (node (ref "R155") (pin "1") (pinfunction "1_1") (pintype "passive"))
    )
    (net (code "22") (name "/STLK_VCP_RX") (class "Default")
      (node (ref "R154") (pin "1") (pinfunction "1_1") (pintype "passive"))
      (node (ref "U36") (pin "C10") (pinfunction "STLK_VCP_RX/PG9_C10") (pintype "passive"))
    )
    (net (code "23") (name "/STLK_VCP_TX") (class "Default")
      (node (ref "R134") (pin "1") (pinfunction "1_1") (pintype "passive"))
      (node (ref "U36") (pin "A7") (pinfunction "STLK_VCP_TX/PG14_A7") (pintype "passive"))
    )
    (net (code "24") (name "/T_JTDI") (class "Default")
      (node (ref "R207") (pin "1") (pinfunction "1_1") (pintype "passive"))
      (node (ref "U36") (pin "L3") (pinfunction "T_JTDI/PF8_L3") (pintype "passive"))
    )
    (net (code "25") (name "/T_PWR_EN") (class "Default")
      (node (ref "R229") (pin "2") (pinfunction "2_2") (pintype "passive"))
      (node (ref "R239") (pin "2") (pinfunction "2_2") (pintype "passive"))
      (node (ref "U36") (pin "R5") (pinfunction "T_PWR_EN/PB0_R5") (pintype "passive"))
      (node (ref "U49") (pin "4") (pinfunction "EN_4") (pintype "passive"))
      (node (ref "U52") (pin "2") (pinfunction "EN/UVLO_2") (pintype "passive"))
    )
    (net (code "26") (name "/T_PWR_EXT") (class "Default")
      (node (ref "R215") (pin "1") (pinfunction "1_1") (pintype "passive"))
      (node (ref "R216") (pin "1") (pinfunction "1_1") (pintype "passive"))
      (node (ref "U36") (pin "R4") (pinfunction "T_PWR_EXT/PB1_R4") (pintype "passive"))
    )
    (net (code "27") (name "/T_PWR_INT") (class "Default")
      (node (ref "C176") (pin "2") (pinfunction "2_2") (pintype "passive"))
      (node (ref "R226") (pin "1") (pinfunction "1_1") (pintype "passive"))
      (node (ref "R227") (pin "2") (pinfunction "2_2") (pintype "passive"))
      (node (ref "R230") (pin "2") (pinfunction "2_2") (pintype "passive"))
      (node (ref "U36") (pin "B13") (pinfunction "T_PWR_INT/PC11_B13") (pintype "passive"))
      (node (ref "U49") (pin "3") (pinfunction "~{FAULT}_3") (pintype "passive"))
    )
    (net (code "28") (name "/T_PWR_LED") (class "Default")
      (node (ref "R132") (pin "2") (pinfunction "2_2") (pintype "passive"))
      (node (ref "R133") (pin "2") (pinfunction "2_2") (pintype "passive"))
      (node (ref "U36") (pin "H15") (pinfunction "T_PWR_LED/PC6_H15") (pintype "passive"))
    )
    (net (code "29") (name "/T_PWR_SEL1") (class "Default")
      (node (ref "R241") (pin "2") (pinfunction "2_2") (pintype "passive"))
      (node (ref "U36") (pin "D10") (pinfunction "T_PWR_SEL1/PD4_D10") (pintype "passive"))
    )
    (net (code "30") (name "/T_PWR_SEL2") (class "Default")
      (node (ref "R240") (pin "2") (pinfunction "2_2") (pintype "passive"))
      (node (ref "U36") (pin "C11") (pinfunction "T_PWR_SEL2/PD5_C11") (pintype "passive"))
    )
    (net (code "31") (name "/T_SWCLK") (class "Default")
      (node (ref "R153") (pin "1") (pinfunction "1_1") (pintype "passive"))
      (node (ref "U36") (pin "A10") (pinfunction "T_JRCLK/PB3_A10") (pintype "passive"))
      (node (ref "U36") (pin "M11") (pinfunction "T_SWCLK/PH6_M11") (pintype "passive"))
      (node (ref "U36") (pin "M6") (pinfunction "T_JCLK_OUT/PB2_M6") (pintype "passive"))
    )
    (net (code "32") (name "/T_SWDIO") (class "Default")
      (node (ref "R209") (pin "1") (pinfunction "1_1") (pintype "passive"))
      (node (ref "U36") (pin "L2") (pinfunction "T_JTMS/T_SWDIO_OUT/PF9_L2") (pintype "passive"))
      (node (ref "U36") (pin "N12") (pinfunction "T_SWDIO_IN/PH7_N12") (pintype "passive"))
    )
    (net (code "33") (name "/T_SWO") (class "Default")
      (node (ref "R129") (pin "1") (pinfunction "1_1") (pintype "passive"))
      (node (ref "U36") (pin "A6") (pinfunction "T_JTDO/PB5_A6") (pintype "passive"))
      (node (ref "U36") (pin "D12") (pinfunction "T_SWO/PD2_D12") (pintype "passive"))
    )
    (net (code "34") (name "/T_VCC") (class "Default")
      (node (ref "LNK13") (pin "2") (pinfunction "2_2") (pintype "passive"))
      (node (ref "R214") (pin "2") (pinfunction "2_2") (pintype "passive"))
    )
    (net (code "35") (name "/T_VCC_AIN") (class "Default")
      (node (ref "R213") (pin "1") (pinfunction "1_1") (pintype "passive"))
      (node (ref "R214") (pin "1") (pinfunction "1_1") (pintype "passive"))
      (node (ref "U36") (pin "N3") (pinfunction "T_VCC_AIN/PA0_N3") (pintype "passive"))
    )
    (net (code "36") (name "3V3_STLK") (class "Default")
      (node (ref "C129") (pin "2") (pinfunction "2_2") (pintype "passive"))
      (node (ref "C281") (pin "1") (pinfunction "1_1") (pintype "passive"))
      (node (ref "C282") (pin "1") (pinfunction "1_1") (pintype "passive"))
      (node (ref "C289") (pin "1") (pinfunction "1_1") (pintype "passive"))
      (node (ref "C290") (pin "1") (pinfunction "1_1") (pintype "passive"))
      (node (ref "C297") (pin "1") (pinfunction "1_1") (pintype "passive"))
      (node (ref "C298") (pin "1") (pinfunction "1_1") (pintype "passive"))
      (node (ref "C299") (pin "1") (pinfunction "1_1") (pintype "passive"))
      (node (ref "C303") (pin "1") (pinfunction "1_1") (pintype "passive"))
      (node (ref "C310") (pin "1") (pinfunction "1_1") (pintype "passive"))
      (node (ref "C311") (pin "1") (pinfunction "1_1") (pintype "passive"))
      (node (ref "C324") (pin "1") (pinfunction "1_1") (pintype "passive"))
      (node (ref "C325") (pin "1") (pinfunction "1_1") (pintype "passive"))
      (node (ref "C326") (pin "1") (pinfunction "1_1") (pintype "passive"))
      (node (ref "C327") (pin "1") (pinfunction "1_1") (pintype "passive"))
      (node (ref "C328") (pin "1") (pinfunction "1_1") (pintype "passive"))
      (node (ref "C329") (pin "1") (pinfunction "1_1") (pintype "passive"))
      (node (ref "C333") (pin "1") (pinfunction "1_1") (pintype "passive"))
      (node (ref "CN14") (pin "1") (pinfunction "1_1") (pintype "passive"))
      (node (ref "LD5") (pin "4") (pinfunction "Green_anode_4") (pintype "passive"))
      (node (ref "LD6") (pin "4") (pinfunction "Green_anode_4") (pintype "passive"))
      (node (ref "R156") (pin "2") (pinfunction "2_2") (pintype "passive"))
      (node (ref "R227") (pin "1") (pinfunction "1_1") (pintype "passive"))
      (node (ref "U35") (pin "1") (pinfunction "VOUT_1") (pintype "passive"))
      (node (ref "U36") (pin "C1") (pinfunction "VBAT_C1") (pintype "passive"))
      (node (ref "U36") (pin "C5") (pinfunction "VDD_C5") (pintype "passive"))
      (node (ref "U36") (pin "C6") (pinfunction "PDR_ON_C6") (pintype "passive"))
      (node (ref "U36") (pin "C7") (pinfunction "VDD_C7") (pintype "passive"))
      (node (ref "U36") (pin "C8") (pinfunction "VDD_C8") (pintype "passive"))
      (node (ref "U36") (pin "C9") (pinfunction "VDD_C9") (pintype "passive"))
      (node (ref "U36") (pin "F3") (pinfunction "VDD_F3") (pintype "passive"))
      (node (ref "U36") (pin "G13") (pinfunction "VDD_G13") (pintype "passive"))
      (node (ref "U36") (pin "G3") (pinfunction "VDD_G3") (pintype "passive"))
      (node (ref "U36") (pin "H13") (pinfunction "VDD_H13") (pintype "passive"))
      (node (ref "U36") (pin "J12") (pinfunction "VDD_J12") (pintype "passive"))
      (node (ref "U36") (pin "J13") (pinfunction "VDD_J13") (pintype "passive"))
      (node (ref "U36") (pin "K4") (pinfunction "VDD_K4") (pintype "passive"))
      (node (ref "U36") (pin "N10") (pinfunction "VDD_N10") (pintype "passive"))
      (node (ref "U36") (pin "N8") (pinfunction "VDD_N8") (pintype "passive"))
      (node (ref "U36") (pin "N9") (pinfunction "VDD_N9") (pintype "passive"))
      (node (ref "U36") (pin "P1") (pinfunction "VREF+_P1") (pintype "passive"))
      (node (ref "U36") (pin "R1") (pinfunction "VDDA_R1") (pintype "passive"))
    )
    (net (code "37") (name "5V_STLK") (class "Default")
      (node (ref "C165") (pin "2") (pinfunction "2_2") (pintype "passive"))
      (node (ref "C169") (pin "2") (pinfunction "2_2") (pintype "passive"))
      (node (ref "C176") (pin "1") (pinfunction "1_1") (pintype "passive"))
      (node (ref "R230") (pin "1") (pinfunction "1_1") (pintype "passive"))
      (node (ref "U49") (pin "1") (pinfunction "OUT_1") (pintype "passive"))
      (node (ref "U52") (pin "5") (pinfunction "OUT_5") (pintype "passive"))
      (node (ref "U52") (pin "6") (pinfunction "QOD_6") (pintype "passive"))
    )
    (net (code "38") (name "5V_VIN") (class "Default")
      (node (ref "D2") (pin "1") (pinfunction "A_1") (pintype "passive"))
      (node (ref "R216") (pin "2") (pinfunction "2_2") (pintype "passive"))
    )
    (net (code "39") (name "GND") (class "Default")
      (node (ref "C110") (pin "1") (pinfunction "1_1") (pintype "passive"))
      (node (ref "C129") (pin "1") (pinfunction "1_1") (pintype "passive"))
      (node (ref "C131") (pin "1") (pinfunction "1_1") (pintype "passive"))
      (node (ref "C132") (pin "1") (pinfunction "1_1") (pintype "passive"))
      (node (ref "C133") (pin "2") (pinfunction "2_2") (pintype "passive"))
      (node (ref "C140") (pin "1") (pinfunction "1_1") (pintype "passive"))
      (node (ref "C145") (pin "1") (pinfunction "1_1") (pintype "passive"))
      (node (ref "C149") (pin "1") (pinfunction "1_1") (pintype "passive"))
      (node (ref "C157") (pin "2") (pinfunction "2_2") (pintype "passive"))
      (node (ref "C158") (pin "2") (pinfunction "2_2") (pintype "passive"))
      (node (ref "C160") (pin "1") (pinfunction "1_1") (pintype "passive"))
      (node (ref "C164") (pin "2") (pinfunction "2_2") (pintype "passive"))
      (node (ref "C165") (pin "1") (pinfunction "1_1") (pintype "passive"))
      (node (ref "C166") (pin "1") (pinfunction "1_1") (pintype "passive"))
      (node (ref "C169") (pin "1") (pinfunction "1_1") (pintype "passive"))
      (node (ref "C172") (pin "1") (pinfunction "1_1") (pintype "passive"))
      (node (ref "C173") (pin "1") (pinfunction "1_1") (pintype "passive"))
      (node (ref "C281") (pin "2") (pinfunction "2_2") (pintype "passive"))
      (node (ref "C282") (pin "2") (pinfunction "2_2") (pintype "passive"))
      (node (ref "C289") (pin "2") (pinfunction "2_2") (pintype "passive"))
      (node (ref "C290") (pin "2") (pinfunction "2_2") (pintype "passive"))
      (node (ref "C297") (pin "2") (pinfunction "2_2") (pintype "passive"))
      (node (ref "C298") (pin "2") (pinfunction "2_2") (pintype "passive"))
      (node (ref "C299") (pin "2") (pinfunction "2_2") (pintype "passive"))
      (node (ref "C303") (pin "2") (pinfunction "2_2") (pintype "passive"))
      (node (ref "C310") (pin "2") (pinfunction "2_2") (pintype "passive"))
      (node (ref "C311") (pin "2") (pinfunction "2_2") (pintype "passive"))
      (node (ref "C324") (pin "2") (pinfunction "2_2") (pintype "passive"))
      (node (ref "C325") (pin "2") (pinfunction "2_2") (pintype "passive"))
      (node (ref "C326") (pin "2") (pinfunction "2_2") (pintype "passive"))
      (node (ref "C327") (pin "2") (pinfunction "2_2") (pintype "passive"))
      (node (ref "C328") (pin "2") (pinfunction "2_2") (pintype "passive"))
      (node (ref "C329") (pin "2") (pinfunction "2_2") (pintype "passive"))
      (node (ref "C333") (pin "2") (pinfunction "2_2") (pintype "passive"))
      (node (ref "CN14") (pin "3") (pinfunction "3_3") (pintype "passive"))
      (node (ref "CN21") (pin "A1") (pinfunction "GND1_A1") (pintype "passive"))
      (node (ref "CN21") (pin "A12") (pinfunction "GND2_A12") (pintype "passive"))
      (node (ref "CN21") (pin "B1") (pinfunction "GND3_B1") (pintype "passive"))
      (node (ref "CN21") (pin "B12") (pinfunction "GND4_B12") (pintype "passive"))
      (node (ref "CN21") (pin "SH1") (pinfunction "Shield1_SH1") (pintype "passive"))
      (node (ref "CN21") (pin "SH2") (pinfunction "Shield2_SH2") (pintype "passive"))
      (node (ref "CN21") (pin "SH3") (pinfunction "Shield3_SH3") (pintype "passive"))
      (node (ref "CN21") (pin "SH4") (pinfunction "Shield4_SH4") (pintype "passive"))
      (node (ref "JP3") (pin "2") (pinfunction "NO_2") (pintype "passive"))
      (node (ref "LD5") (pin "3") (pinfunction "RED_cathode_3") (pintype "passive"))
      (node (ref "LD6") (pin "3") (pinfunction "RED_cathode_3") (pintype "passive"))
      (node (ref "R194") (pin "2") (pinfunction "2_2") (pintype "passive"))
      (node (ref "R213") (pin "2") (pinfunction "2_2") (pintype "passive"))
      (node (ref "R215") (pin "2") (pinfunction "2_2") (pintype "passive"))
      (node (ref "R221") (pin "2") (pinfunction "2_2") (pintype "passive"))
      (node (ref "R222") (pin "2") (pinfunction "2_2") (pintype "passive"))
      (node (ref "R226") (pin "2") (pinfunction "2_2") (pintype "passive"))
      (node (ref "R229") (pin "1") (pinfunction "1_1") (pintype "passive"))
      (node (ref "R239") (pin "1") (pinfunction "1_1") (pintype "passive"))
      (node (ref "R242") (pin "2") (pinfunction "2_2") (pintype "passive"))
      (node (ref "U35") (pin "2") (pinfunction "GND_2") (pintype "passive"))
      (node (ref "U36") (pin "D5") (pinfunction "VSS_D5") (pintype "passive"))
      (node (ref "U36") (pin "D6") (pinfunction "BOOT0_D6") (pintype "passive"))
      (node (ref "U36") (pin "D7") (pinfunction "VSS_D7") (pintype "passive"))
      (node (ref "U36") (pin "D8") (pinfunction "VSS_D8") (pintype "passive"))
      (node (ref "U36") (pin "D9") (pinfunction "VSS_D9") (pintype "passive"))
      (node (ref "U36") (pin "F10") (pinfunction "VSS_F10") (pintype "passive"))
      (node (ref "U36") (pin "F12") (pinfunction "VSS_F12") (pintype "passive"))
      (node (ref "U36") (pin "F2") (pinfunction "VSS_F2") (pintype "passive"))
      (node (ref "U36") (pin "F6") (pinfunction "VSS_F6") (pintype "passive"))
      (node (ref "U36") (pin "F7") (pinfunction "VSS_F7") (pintype "passive"))
      (node (ref "U36") (pin "F8") (pinfunction "VSS_F8") (pintype "passive"))
      (node (ref "U36") (pin "F9") (pinfunction "VSS_F9") (pintype "passive"))
      (node (ref "U36") (pin "G10") (pinfunction "VSS_G10") (pintype "passive"))
      (node (ref "U36") (pin "G12") (pinfunction "VSS_G12") (pintype "passive"))
      (node (ref "U36") (pin "G2") (pinfunction "VSS_G2") (pintype "passive"))
      (node (ref "U36") (pin "G6") (pinfunction "VSS_G6") (pintype "passive"))
      (node (ref "U36") (pin "G7") (pinfunction "VSS_G7") (pintype "passive"))
      (node (ref "U36") (pin "G8") (pinfunction "VSS_G8") (pintype "passive"))
      (node (ref "U36") (pin "G9") (pinfunction "VSS_G9") (pintype "passive"))
      (node (ref "U36") (pin "H10") (pinfunction "VSS_H10") (pintype "passive"))
      (node (ref "U36") (pin "H12") (pinfunction "VSS_H12") (pintype "passive"))
      (node (ref "U36") (pin "H6") (pinfunction "VSS_H6") (pintype "passive"))
      (node (ref "U36") (pin "H7") (pinfunction "VSS_H7") (pintype "passive"))
      (node (ref "U36") (pin "H8") (pinfunction "VSS_H8") (pintype "passive"))
      (node (ref "U36") (pin "H9") (pinfunction "VSS_H9") (pintype "passive"))
      (node (ref "U36") (pin "J10") (pinfunction "VSS_J10") (pintype "passive"))
      (node (ref "U36") (pin "J6") (pinfunction "VSS_J6") (pintype "passive"))
      (node (ref "U36") (pin "J7") (pinfunction "VSS_J7") (pintype "passive"))
      (node (ref "U36") (pin "J8") (pinfunction "VSS_J8") (pintype "passive"))
      (node (ref "U36") (pin "J9") (pinfunction "VSS_J9") (pintype "passive"))
      (node (ref "U36") (pin "K10") (pinfunction "VSS_K10") (pintype "passive"))
      (node (ref "U36") (pin "K6") (pinfunction "VSS_K6") (pintype "passive"))
      (node (ref "U36") (pin "K7") (pinfunction "VSS_K7") (pintype "passive"))
      (node (ref "U36") (pin "K8") (pinfunction "VSS_K8") (pintype "passive"))
      (node (ref "U36") (pin "K9") (pinfunction "VSS_K9") (pintype "passive"))
      (node (ref "U36") (pin "L4") (pinfunction "BYPASS-REG_L4") (pintype "passive"))
      (node (ref "U36") (pin "M1") (pinfunction "VSSA_M1") (pintype "passive"))
      (node (ref "U36") (pin "M8") (pinfunction "VSS_M8") (pintype "passive"))
      (node (ref "U36") (pin "M9") (pinfunction "VSS_M9") (pintype "passive"))
      (node (ref "U36") (pin "N1") (pinfunction "VREF-_N1") (pintype "passive"))
      (node (ref "U47") (pin "3") (pinfunction "GND_3") (pintype "passive"))
      (node (ref "U48") (pin "2") (pinfunction "GND_2") (pintype "passive"))
      (node (ref "U49") (pin "2") (pinfunction "GND_2") (pintype "passive"))
      (node (ref "U52") (pin "8") (pinfunction "GND_8") (pintype "passive"))
      (node (ref "U52") (pin "9") (pinfunction "EP_9") (pintype "passive"))
      (node (ref "X7") (pin "2") (pinfunction "2_2") (pintype "passive"))
      (node (ref "X7") (pin "4") (pinfunction "4_4") (pintype "passive"))
    )
    (net (code "40") (name "Net-(C131-Pad2)") (class "Default")
      (node (ref "C131") (pin "2") (pinfunction "2_2") (pintype "passive"))
      (node (ref "R181") (pin "2") (pinfunction "2_2") (pintype "passive"))
      (node (ref "TP33") (pin "1") (pinfunction "1_1") (pintype "passive"))
    )
    (net (code "41") (name "Net-(CN21-CC1)") (class "Default")
      (node (ref "CN21") (pin "A5") (pinfunction "CC1_A5") (pintype "passive"))
      (node (ref "R217") (pin "2") (pinfunction "2_2") (pintype "passive"))
      (node (ref "R221") (pin "1") (pinfunction "1_1") (pintype "passive"))
    )
    (net (code "42") (name "Net-(CN21-CC2)") (class "Default")
      (node (ref "CN21") (pin "B5") (pinfunction "CC2_B5") (pintype "passive"))
      (node (ref "R218") (pin "2") (pinfunction "2_2") (pintype "passive"))
      (node (ref "R222") (pin "1") (pinfunction "1_1") (pintype "passive"))
    )
    (net (code "43") (name "Net-(D2-K)") (class "Default")
      (node (ref "C110") (pin "2") (pinfunction "2_2") (pintype "passive"))
      (node (ref "D2") (pin "2") (pinfunction "K_2") (pintype "passive"))
      (node (ref "D3") (pin "2") (pinfunction "K_2") (pintype "passive"))
      (node (ref "U35") (pin "3") (pinfunction "VIN_3") (pintype "passive"))
      (node (ref "U35") (pin "5") (pinfunction "EN_5") (pintype "passive"))
    )
    (net (code "44") (name "Net-(LD5-Green_cathode)") (class "Default")
      (node (ref "LD5") (pin "2") (pinfunction "Green_cathode_2") (pintype "passive"))
      (node (ref "R130") (pin "2") (pinfunction "2_2") (pintype "passive"))
    )
    (net (code "45") (name "Net-(LD5-Red_anode)") (class "Default")
      (node (ref "LD5") (pin "1") (pinfunction "Red_anode_1") (pintype "passive"))
      (node (ref "R131") (pin "1") (pinfunction "1_1") (pintype "passive"))
    )
    (net (code "46") (name "Net-(LD6-Green_cathode)") (class "Default")
      (node (ref "LD6") (pin "2") (pinfunction "Green_cathode_2") (pintype "passive"))
      (node (ref "R132") (pin "1") (pinfunction "1_1") (pintype "passive"))
    )
    (net (code "47") (name "Net-(LD6-Red_anode)") (class "Default")
      (node (ref "LD6") (pin "1") (pinfunction "Red_anode_1") (pintype "passive"))
      (node (ref "R133") (pin "1") (pinfunction "1_1") (pintype "passive"))
    )
    (net (code "48") (name "Net-(U36A-HW_TYP_0{slash}PI4)") (class "Default")
      (node (ref "R156") (pin "1") (pinfunction "1_1") (pintype "passive"))
      (node (ref "U36") (pin "D4") (pinfunction "HW_TYP_0/PI4_D4") (pintype "passive"))
    )
    (net (code "49") (name "Net-(U36A-REXT_OTGPHY)") (class "Default")
      (node (ref "R194") (pin "1") (pinfunction "1_1") (pintype "passive"))
      (node (ref "U36") (pin "J15") (pinfunction "REXT_OTGPHY_J15") (pintype "passive"))
    )
    (net (code "50") (name "Net-(U36A-T_MCO{slash}PA8)") (class "Default")
      (node (ref "R181") (pin "1") (pinfunction "1_1") (pintype "passive"))
      (node (ref "U36") (pin "F15") (pinfunction "T_MCO/PA8_F15") (pintype "passive"))
    )
    (net (code "51") (name "Net-(U36A-T_NRST{slash}PA6)") (class "Default")
      (node (ref "R212") (pin "1") (pinfunction "1_1") (pintype "passive"))
      (node (ref "U36") (pin "P3") (pinfunction "T_NRST/PA6_P3") (pintype "passive"))
    )
    (net (code "52") (name "Net-(U36A-V12_OTGPHY)") (class "Default")
      (node (ref "C145") (pin "2") (pinfunction "2_2") (pintype "passive"))
      (node (ref "U36") (pin "J14") (pinfunction "V12_OTGPHY_J14") (pintype "passive"))
    )
    (net (code "53") (name "Net-(U36B-VCAP1)") (class "Default")
      (node (ref "C160") (pin "2") (pinfunction "2_2") (pintype "passive"))
      (node (ref "U36") (pin "M10") (pinfunction "VCAP1_M10") (pintype "passive"))
    )
    (net (code "54") (name "Net-(U36B-VCAP2)") (class "Default")
      (node (ref "C132") (pin "2") (pinfunction "2_2") (pintype "passive"))
      (node (ref "U36") (pin "F13") (pinfunction "VCAP2_F13") (pintype "passive"))
    )
    (net (code "55") (name "Net-(U36C-GPIO0{slash}PE2)") (class "Default")
      (node (ref "TP29") (pin "1") (pinfunction "1_1") (pintype "passive"))
      (node (ref "U36") (pin "A2") (pinfunction "GPIO0/PE2_A2") (pintype "passive"))
    )
    (net (code "56") (name "Net-(U36C-GPIO1{slash}PE4)") (class "Default")
      (node (ref "TP28") (pin "1") (pinfunction "1_1") (pintype "passive"))
      (node (ref "U36") (pin "B1") (pinfunction "GPIO1/PE4_B1") (pintype "passive"))
    )
    (net (code "57") (name "Net-(U36C-GPIO2{slash}PE5)") (class "Default")
      (node (ref "TP26") (pin "1") (pinfunction "1_1") (pintype "passive"))
      (node (ref "U36") (pin "B2") (pinfunction "GPIO2/PE5_B2") (pintype "passive"))
    )
    (net (code "58") (name "Net-(U36C-GPIO3{slash}PE6)") (class "Default")
      (node (ref "TP27") (pin "1") (pinfunction "1_1") (pintype "passive"))
      (node (ref "U36") (pin "B3") (pinfunction "GPIO3/PE6_B3") (pintype "passive"))
    )
    (net (code "59") (name "Net-(U36C-UART_RX{slash}PB11)") (class "Default")
      (node (ref "R211") (pin "2") (pinfunction "2_2") (pintype "passive"))
      (node (ref "U36") (pin "R13") (pinfunction "UART_RX/PB11_R13") (pintype "passive"))
    )
    (net (code "60") (name "Net-(U36C-UART_TX{slash}PC10)") (class "Default")
      (node (ref "R155") (pin "2") (pinfunction "2_2") (pintype "passive"))
      (node (ref "U36") (pin "B14") (pinfunction "UART_TX/PC10_B14") (pintype "passive"))
    )
    (net (code "61") (name "Net-(U52-ILM)") (class "Default")
      (node (ref "R240") (pin "1") (pinfunction "1_1") (pintype "passive"))
      (node (ref "R241") (pin "1") (pinfunction "1_1") (pintype "passive"))
      (node (ref "R242") (pin "1") (pinfunction "1_1") (pintype "passive"))
      (node (ref "U52") (pin "7") (pinfunction "ILM_7") (pintype "passive"))
    )
    (net (code "62") (name "Net-(U52-dVdt)") (class "Default")
      (node (ref "C173") (pin "2") (pinfunction "2_2") (pintype "passive"))
      (node (ref "U52") (pin "1") (pinfunction "dVdt_1") (pintype "passive"))
    )
    (net (code "63") (name "VBUS_STLK") (class "Default")
      (node (ref "C164") (pin "1") (pinfunction "1_1") (pintype "passive"))
      (node (ref "C166") (pin "2") (pinfunction "2_2") (pintype "passive"))
      (node (ref "C172") (pin "2") (pinfunction "2_2") (pintype "passive"))
      (node (ref "CN21") (pin "A4") (pinfunction "VBUS1_A4") (pintype "passive"))
      (node (ref "CN21") (pin "A9") (pinfunction "VBUS2_A9") (pintype "passive"))
      (node (ref "CN21") (pin "B4") (pinfunction "VBUS3_B4") (pintype "passive"))
      (node (ref "CN21") (pin "B9") (pinfunction "VBUS4_B9") (pintype "passive"))
      (node (ref "D3") (pin "1") (pinfunction "A_1") (pintype "passive"))
      (node (ref "U48") (pin "1") (pinfunction "IO1_1") (pintype "passive"))
      (node (ref "U49") (pin "5") (pinfunction "IN_5") (pintype "passive"))
      (node (ref "U52") (pin "3") (pinfunction "IN_3") (pintype "passive"))
      (node (ref "U52") (pin "4") (pinfunction "IN_4") (pintype "passive"))
    )
    (net (code "64") (name "VDDIO") (class "Default")
      (node (ref "LNK13") (pin "1") (pinfunction "1_1") (pintype "passive"))
    )
    (net (code "65") (name "unconnected-(CN21-RX1+-PadB11)") (class "Default")
      (node (ref "CN21") (pin "B11") (pinfunction "RX1+_B11") (pintype "passive+no_connect"))
    )
    (net (code "66") (name "unconnected-(CN21-RX1--PadB10)") (class "Default")
      (node (ref "CN21") (pin "B10") (pinfunction "RX1-_B10") (pintype "passive+no_connect"))
    )
    (net (code "67") (name "unconnected-(CN21-RX2+-PadA11)") (class "Default")
      (node (ref "CN21") (pin "A11") (pinfunction "RX2+_A11") (pintype "passive+no_connect"))
    )
    (net (code "68") (name "unconnected-(CN21-RX2--PadA10)") (class "Default")
      (node (ref "CN21") (pin "A10") (pinfunction "RX2-_A10") (pintype "passive+no_connect"))
    )
    (net (code "69") (name "unconnected-(CN21-SBU1-PadA8)") (class "Default")
      (node (ref "CN21") (pin "A8") (pinfunction "SBU1_A8") (pintype "passive+no_connect"))
    )
    (net (code "70") (name "unconnected-(CN21-SBU2-PadB8)") (class "Default")
      (node (ref "CN21") (pin "B8") (pinfunction "SBU2_B8") (pintype "passive+no_connect"))
    )
    (net (code "71") (name "unconnected-(CN21-TX1+-PadA2)") (class "Default")
      (node (ref "CN21") (pin "A2") (pinfunction "TX1+_A2") (pintype "passive+no_connect"))
    )
    (net (code "72") (name "unconnected-(CN21-TX1--PadA3)") (class "Default")
      (node (ref "CN21") (pin "A3") (pinfunction "TX1-_A3") (pintype "passive+no_connect"))
    )
    (net (code "73") (name "unconnected-(CN21-TX2+-PadB2)") (class "Default")
      (node (ref "CN21") (pin "B2") (pinfunction "TX2+_B2") (pintype "passive+no_connect"))
    )
    (net (code "74") (name "unconnected-(CN21-TX2--PadB3)") (class "Default")
      (node (ref "CN21") (pin "B3") (pinfunction "TX2-_B3") (pintype "passive+no_connect"))
    )
    (net (code "75") (name "unconnected-(U35-NC{slash}ADJ-Pad4)") (class "Default")
      (node (ref "U35") (pin "4") (pinfunction "NC/ADJ_4") (pintype "passive+no_connect"))
    )
    (net (code "76") (name "unconnected-(U36A-GNDDetect{slash}PG5-PadK13)") (class "Default")
      (node (ref "U36") (pin "K13") (pinfunction "GNDDetect/PG5_K13") (pintype "passive+no_connect"))
    )
    (net (code "77") (name "unconnected-(U36A-HW_TYP_1{slash}PI5-PadC4)") (class "Default")
      (node (ref "U36") (pin "C4") (pinfunction "HW_TYP_1/PI5_C4") (pintype "passive+no_connect"))
    )
    (net (code "78") (name "unconnected-(U36A-T_JNRST{slash}PF13-PadN6)") (class "Default")
      (node (ref "U36") (pin "N6") (pinfunction "T_JNRST/PF13_N6") (pintype "passive+no_connect"))
    )
    (net (code "79") (name "unconnected-(U36A-T_SW_DIR{slash}PA7-PadR3)") (class "Default")
      (node (ref "U36") (pin "R3") (pinfunction "T_SW_DIR/PA7_R3") (pintype "passive+no_connect"))
    )
    (net (code "80") (name "unconnected-(U36C-CAN_RX{slash}PA11-PadC15)") (class "Default")
      (node (ref "U36") (pin "C15") (pinfunction "CAN_RX/PA11_C15") (pintype "passive+no_connect"))
    )
    (net (code "81") (name "unconnected-(U36C-CAN_TX{slash}PA12-PadB15)") (class "Default")
      (node (ref "U36") (pin "B15") (pinfunction "CAN_TX/PA12_B15") (pintype "passive+no_connect"))
    )
    (net (code "82") (name "unconnected-(U36C-I2C_SCL{slash}PB8-PadA5)") (class "Default")
      (node (ref "U36") (pin "A5") (pinfunction "I2C_SCL/PB8_A5") (pintype "passive+no_connect"))
    )
    (net (code "83") (name "unconnected-(U36C-I2C_SDA{slash}PB9-PadB4)") (class "Default")
      (node (ref "U36") (pin "B4") (pinfunction "I2C_SDA/PB9_B4") (pintype "passive+no_connect"))
    )
    (net (code "84") (name "unconnected-(U36C-SPI_MISO{slash}PC2-PadM4)") (class "Default")
      (node (ref "U36") (pin "M4") (pinfunction "SPI_MISO/PC2_M4") (pintype "passive+no_connect"))
    )
    (net (code "85") (name "unconnected-(U36C-SPI_MOSI{slash}PC1-PadM3)") (class "Default")
      (node (ref "U36") (pin "M3") (pinfunction "SPI_MOSI/PC1_M3") (pintype "passive+no_connect"))
    )
    (net (code "86") (name "unconnected-(U36C-SPI_NSS{slash}PB4-PadA9)") (class "Default")
      (node (ref "U36") (pin "A9") (pinfunction "SPI_NSS/PB4_A9") (pintype "passive+no_connect"))
    )
    (net (code "87") (name "unconnected-(U36C-SPI_SCK{slash}PA9-PadE15)") (class "Default")
      (node (ref "U36") (pin "E15") (pinfunction "SPI_SCK/PA9_E15") (pintype "passive+no_connect"))
    )
    (net (code "88") (name "unconnected-(U36C-UART_CTS{slash}PD11-PadN14)") (class "Default")
      (node (ref "U36") (pin "N14") (pinfunction "UART_CTS/PD11_N14") (pintype "passive+no_connect"))
    )
    (net (code "89") (name "unconnected-(U36C-UART_RTS{slash}PD12-PadN13)") (class "Default")
      (node (ref "U36") (pin "N13") (pinfunction "UART_RTS/PD12_N13") (pintype "passive+no_connect"))
    )
    (net (code "90") (name "unconnected-(U47-NC-Pad4)") (class "Default")
      (node (ref "U47") (pin "4") (pinfunction "NC_4") (pintype "passive+no_connect"))
    )
  )
)
